# control_sonar_logic.net
KiCad netlist of a schematic drawn in Altium Designer
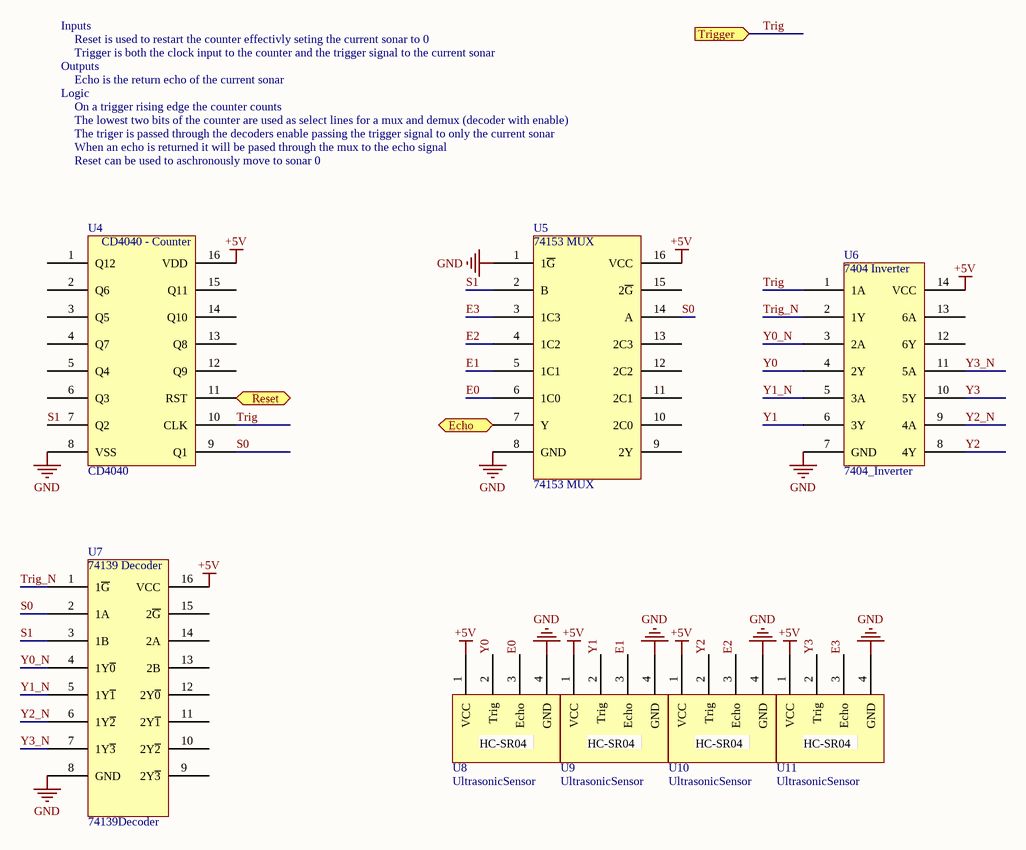
[diagram p0: control_sonar_logic.SchDoc]

(export (version "E")
  (design (tool "Eeschema 10.0.6"))
  (components
    (comp (ref "U4") (value "CD4040") (footprint "DIP-16") (libsource (lib "control_board") (part "CD4040")))
    (comp (ref "U5")
      (value "74153 MUX")
      (footprint "DIP-16")
      (libsource (lib "control_board") (part "74153 MUX"))
    )
    (comp (ref "U6")
      (value "7404_Inverter")
      (footprint "DIP-14")
      (libsource (lib "control_board") (part "7404_Inverter"))
    )
    (comp (ref "U7")
      (value "74139Decoder")
      (footprint "DIP-16")
      (libsource (lib "control_board") (part "74139Decoder"))
    )
    (comp (ref "U8")
      (value "UltrasonicSensor")
      (footprint "HDR1X4")
      (libsource (lib "control_board") (part "UltrasonicSensor"))
    )
    (comp (ref "U9")
      (value "UltrasonicSensor")
      (footprint "HDR1X4")
      (libsource (lib "control_board") (part "UltrasonicSensor"))
    )
    (comp (ref "U10")
      (value "UltrasonicSensor")
      (footprint "HDR1X4")
      (libsource (lib "control_board") (part "UltrasonicSensor"))
    )
    (comp (ref "U11")
      (value "UltrasonicSensor")
      (footprint "HDR1X4")
      (libsource (lib "control_board") (part "UltrasonicSensor"))
    )
  )
  (nets
    (net (code "1") (name "+5V") (class "Default")
      (node (ref "U10") (pin "1") (pinfunction "VCC_1") (pintype "passive"))
      (node (ref "U11") (pin "1") (pinfunction "VCC_1") (pintype "passive"))
      (node (ref "U4") (pin "16") (pinfunction "VDD_16") (pintype "passive"))
      (node (ref "U5") (pin "16") (pinfunction "VCC_16") (pintype "passive"))
      (node (ref "U6") (pin "14") (pinfunction "VCC_14") (pintype "passive"))
      (node (ref "U7") (pin "16") (pinfunction "VCC_16") (pintype "passive"))
      (node (ref "U8") (pin "1") (pinfunction "VCC_1") (pintype "passive"))
      (node (ref "U9") (pin "1") (pinfunction "VCC_1") (pintype "passive"))
    )
    (net (code "2") (name "/E0") (class "Default")
      (node (ref "U5") (pin "6") (pinfunction "1C0_6") (pintype "passive"))
      (node (ref "U8") (pin "3") (pinfunction "Echo_3") (pintype "passive"))
    )
    (net (code "3") (name "/E1") (class "Default")
      (node (ref "U5") (pin "5") (pinfunction "1C1_5") (pintype "passive"))
      (node (ref "U9") (pin "3") (pinfunction "Echo_3") (pintype "passive"))
    )
    (net (code "4") (name "/E2") (class "Default")
      (node (ref "U10") (pin "3") (pinfunction "Echo_3") (pintype "passive"))
      (node (ref "U5") (pin "4") (pinfunction "1C2_4") (pintype "passive"))
    )
    (net (code "5") (name "/E3") (class "Default")
      (node (ref "U11") (pin "3") (pinfunction "Echo_3") (pintype "passive"))
      (node (ref "U5") (pin "3") (pinfunction "1C3_3") (pintype "passive"))
    )
    (net (code "6") (name "/Echo") (class "Default")
      (node (ref "U5") (pin "7") (pinfunction "Y_7") (pintype "passive"))
    )
    (net (code "7") (name "/Reset") (class "Default")
      (node (ref "U4") (pin "11") (pinfunction "RST_11") (pintype "passive"))
    )
    (net (code "8") (name "/S0") (class "Default")
      (node (ref "U4") (pin "9") (pinfunction "Q1_9") (pintype "passive"))
      (node (ref "U5") (pin "14") (pinfunction "A_14") (pintype "passive"))
      (node (ref "U7") (pin "2") (pinfunction "1A_2") (pintype "passive"))
    )
    (net (code "9") (name "/S1") (class "Default")
      (node (ref "U4") (pin "7") (pinfunction "Q2_7") (pintype "passive"))
      (node (ref "U5") (pin "2") (pinfunction "B_2") (pintype "passive"))
      (node (ref "U7") (pin "3") (pinfunction "1B_3") (pintype "passive"))
    )
    (net (code "10") (name "/Trig") (class "Default")
      (node (ref "U4") (pin "10") (pinfunction "CLK_10") (pintype "passive"))
      (node (ref "U6") (pin "1") (pinfunction "1A_1") (pintype "passive"))
    )
    (net (code "11") (name "/Trig_N") (class "Default")
      (node (ref "U6") (pin "2") (pinfunction "1Y_2") (pintype "passive"))
      (node (ref "U7") (pin "1") (pinfunction "1~{G}_1") (pintype "passive"))
    )
    (net (code "12") (name "/Y0") (class "Default")
      (node (ref "U6") (pin "4") (pinfunction "2Y_4") (pintype "passive"))
      (node (ref "U8") (pin "2") (pinfunction "Trig_2") (pintype "passive"))
    )
    (net (code "13") (name "/Y0_N") (class "Default")
      (node (ref "U6") (pin "3") (pinfunction "2A_3") (pintype "passive"))
      (node (ref "U7") (pin "4") (pinfunction "1Y~{0}_4") (pintype "passive"))
    )
    (net (code "14") (name "/Y1") (class "Default")
      (node (ref "U6") (pin "6") (pinfunction "3Y_6") (pintype "passive"))
      (node (ref "U9") (pin "2") (pinfunction "Trig_2") (pintype "passive"))
    )
    (net (code "15") (name "/Y1_N") (class "Default")
      (node (ref "U6") (pin "5") (pinfunction "3A_5") (pintype "passive"))
      (node (ref "U7") (pin "5") (pinfunction "1Y~{1}_5") (pintype "passive"))
    )
    (net (code "16") (name "/Y2") (class "Default")
      (node (ref "U10") (pin "2") (pinfunction "Trig_2") (pintype "passive"))
      (node (ref "U6") (pin "8") (pinfunction "4Y_8") (pintype "passive"))
    )
    (net (code "17") (name "/Y2_N") (class "Default")
      (node (ref "U6") (pin "9") (pinfunction "4A_9") (pintype "passive"))
      (node (ref "U7") (pin "6") (pinfunction "1Y~{2}_6") (pintype "passive"))
    )
    (net (code "18") (name "/Y3") (class "Default")
      (node (ref "U11") (pin "2") (pinfunction "Trig_2") (pintype "passive"))
      (node (ref "U6") (pin "10") (pinfunction "5Y_10") (pintype "passive"))
    )
    (net (code "19") (name "/Y3_N") (class "Default")
      (node (ref "U6") (pin "11") (pinfunction "5A_11") (pintype "passive"))
      (node (ref "U7") (pin "7") (pinfunction "1Y~{3}_7") (pintype "passive"))
    )
    (net (code "20") (name "GND") (class "Default")
      (node (ref "U10") (pin "4") (pinfunction "GND_4") (pintype "passive"))
      (node (ref "U11") (pin "4") (pinfunction "GND_4") (pintype "passive"))
      (node (ref "U4") (pin "8") (pinfunction "VSS_8") (pintype "passive"))
      (node (ref "U5") (pin "1") (pinfunction "1~{G}_1") (pintype "passive"))
      (node (ref "U5") (pin "8") (pinfunction "GND_8") (pintype "passive"))
      (node (ref "U6") (pin "7") (pinfunction "GND_7") (pintype "passive"))
      (node (ref "U7") (pin "8") (pinfunction "GND_8") (pintype "passive"))
      (node (ref "U8") (pin "4") (pinfunction "GND_4") (pintype "passive"))
      (node (ref "U9") (pin "4") (pinfunction "GND_4") (pintype "passive"))
    )
    (net (code "21") (name "unconnected-(U4-Q3-Pad6)") (class "Default")
      (node (ref "U4") (pin "6") (pinfunction "Q3_6") (pintype "passive"))
    )
    (net (code "22") (name "unconnected-(U4-Q4-Pad5)") (class "Default")
      (node (ref "U4") (pin "5") (pinfunction "Q4_5") (pintype "passive"))
    )
    (net (code "23") (name "unconnected-(U4-Q5-Pad3)") (class "Default")
      (node (ref "U4") (pin "3") (pinfunction "Q5_3") (pintype "passive"))
    )
    (net (code "24") (name "unconnected-(U4-Q6-Pad2)") (class "Default")
      (node (ref "U4") (pin "2") (pinfunction "Q6_2") (pintype "passive"))
    )
    (net (code "25") (name "unconnected-(U4-Q7-Pad4)") (class "Default")
      (node (ref "U4") (pin "4") (pinfunction "Q7_4") (pintype "passive"))
    )
    (net (code "26") (name "unconnected-(U4-Q8-Pad13)") (class "Default")
      (node (ref "U4") (pin "13") (pinfunction "Q8_13") (pintype "passive"))
    )
    (net (code "27") (name "unconnected-(U4-Q9-Pad12)") (class "Default")
      (node (ref "U4") (pin "12") (pinfunction "Q9_12") (pintype "passive"))
    )
    (net (code "28") (name "unconnected-(U4-Q10-Pad14)") (class "Default")
      (node (ref "U4") (pin "14") (pinfunction "Q10_14") (pintype "passive"))
    )
    (net (code "29") (name "unconnected-(U4-Q11-Pad15)") (class "Default")
      (node (ref "U4") (pin "15") (pinfunction "Q11_15") (pintype "passive"))
    )
    (net (code "30") (name "unconnected-(U4-Q12-Pad1)") (class "Default")
      (node (ref "U4") (pin "1") (pinfunction "Q12_1") (pintype "passive"))
    )
    (net (code "31") (name "unconnected-(U5-2C0-Pad10)") (class "Default")
      (node (ref "U5") (pin "10") (pinfunction "2C0_10") (pintype "passive"))
    )
    (net (code "32") (name "unconnected-(U5-2C1-Pad11)") (class "Default")
      (node (ref "U5") (pin "11") (pinfunction "2C1_11") (pintype "passive"))
    )
    (net (code "33") (name "unconnected-(U5-2C2-Pad12)") (class "Default")
      (node (ref "U5") (pin "12") (pinfunction "2C2_12") (pintype "passive"))
    )
    (net (code "34") (name "unconnected-(U5-2C3-Pad13)") (class "Default")
      (node (ref "U5") (pin "13") (pinfunction "2C3_13") (pintype "passive"))
    )
    (net (code "35") (name "unconnected-(U5-2Y-Pad9)") (class "Default")
      (node (ref "U5") (pin "9") (pinfunction "2Y_9") (pintype "passive"))
    )
    (net (code "36") (name "unconnected-(U5-2~{G}-Pad15)") (class "Default")
      (node (ref "U5") (pin "15") (pinfunction "2~{G}_15") (pintype "passive"))
    )
    (net (code "37") (name "unconnected-(U6-6A-Pad13)") (class "Default")
      (node (ref "U6") (pin "13") (pinfunction "6A_13") (pintype "passive"))
    )
    (net (code "38") (name "unconnected-(U6-6Y-Pad12)") (class "Default")
      (node (ref "U6") (pin "12") (pinfunction "6Y_12") (pintype "passive"))
    )
    (net (code "39") (name "unconnected-(U7-2A-Pad14)") (class "Default")
      (node (ref "U7") (pin "14") (pinfunction "2A_14") (pintype "passive"))
    )
    (net (code "40") (name "unconnected-(U7-2B-Pad13)") (class "Default")
      (node (ref "U7") (pin "13") (pinfunction "2B_13") (pintype "passive"))
    )
    (net (code "41") (name "unconnected-(U7-2Y~{0}-Pad12)") (class "Default")
      (node (ref "U7") (pin "12") (pinfunction "2Y~{0}_12") (pintype "passive"))
    )
    (net (code "42") (name "unconnected-(U7-2Y~{1}-Pad11)") (class "Default")
      (node (ref "U7") (pin "11") (pinfunction "2Y~{1}_11") (pintype "passive"))
    )
    (net (code "43") (name "unconnected-(U7-2Y~{2}-Pad10)") (class "Default")
      (node (ref "U7") (pin "10") (pinfunction "2Y~{2}_10") (pintype "passive"))
    )
    (net (code "44") (name "unconnected-(U7-2Y~{3}-Pad9)") (class "Default")
      (node (ref "U7") (pin "9") (pinfunction "2Y~{3}_9") (pintype "passive"))
    )
    (net (code "45") (name "unconnected-(U7-2~{G}-Pad15)") (class "Default")
      (node (ref "U7") (pin "15") (pinfunction "2~{G}_15") (pintype "passive"))
    )
  )
)
